# cc2540.net
KiCad netlist of a schematic drawn in EAGLE
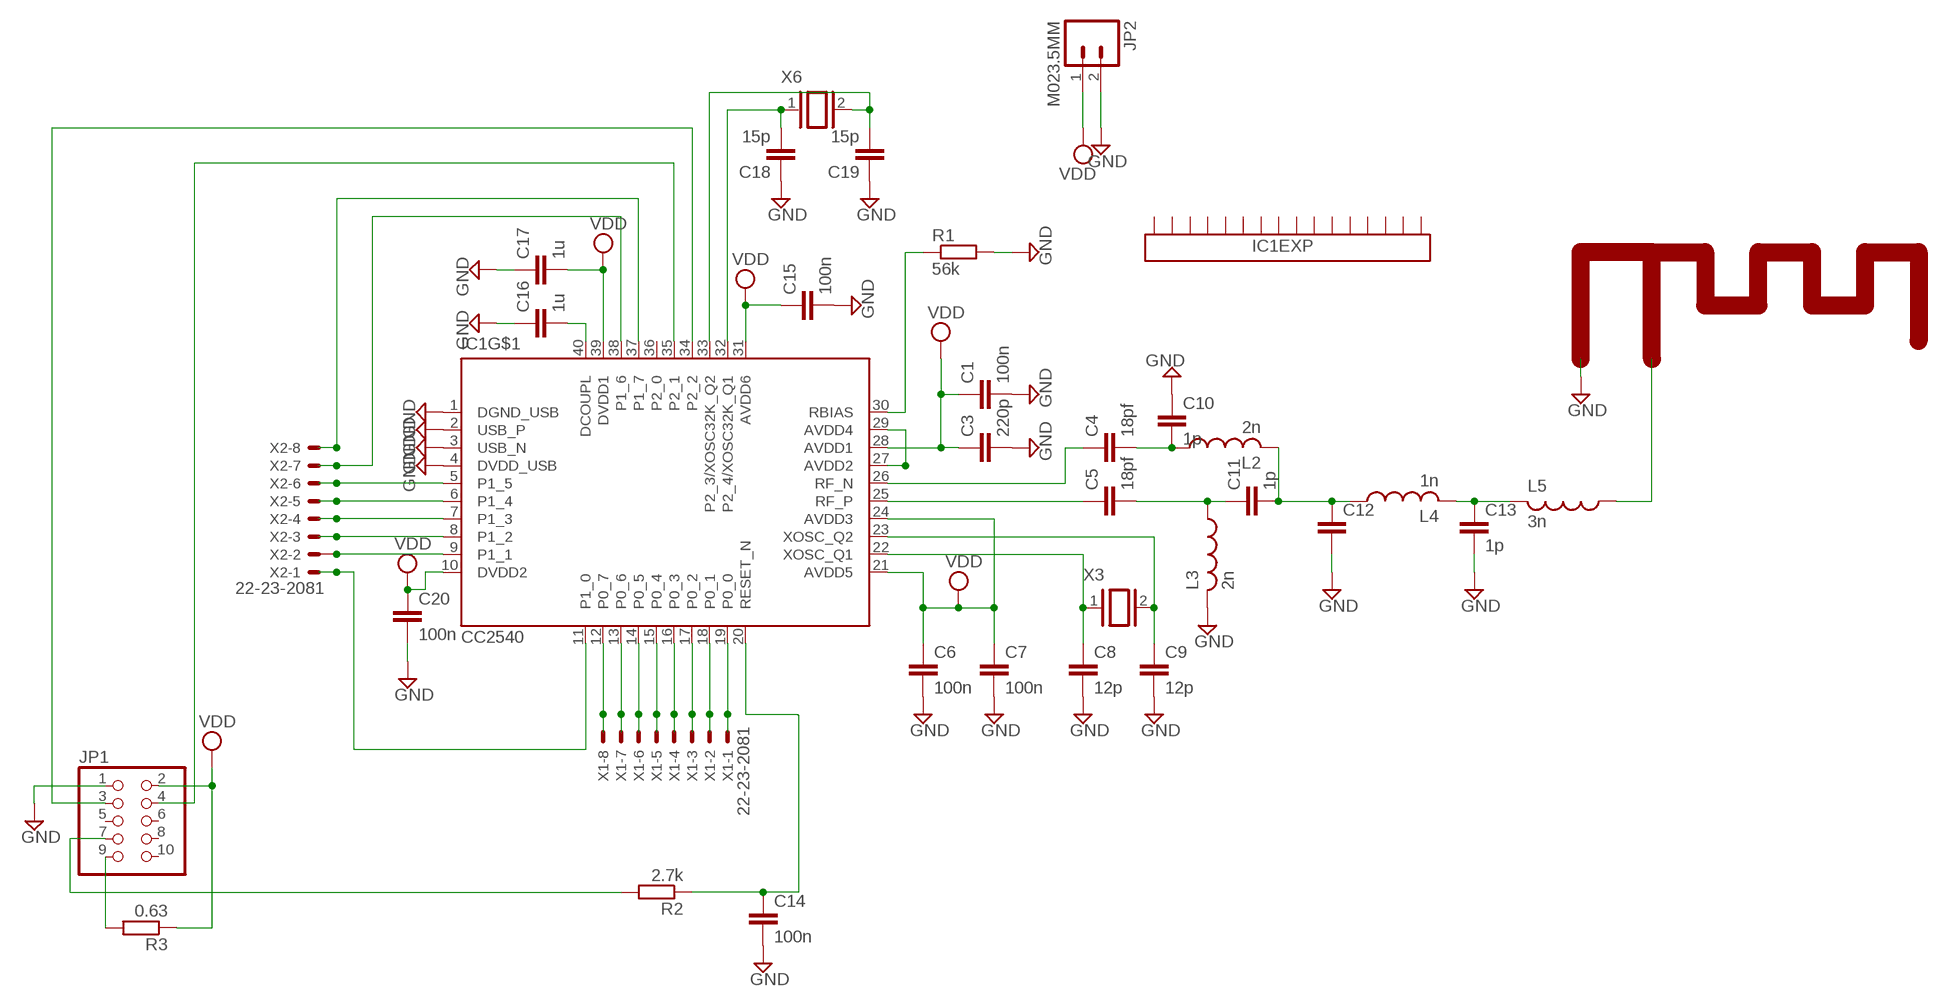
[diagram p0: schematic, sheet 1]

(export (version "E")
  (design (tool "Eeschema 10.0.6"))
  (components
    (comp (ref "A1")
      (value "TI_2.4GHZ_MIFALEFT")
      (footprint "eagle-import:TI_2.4GHZ_MIFA_LEFT")
      (libsource (lib "eagle-import") (part "TI_2.4GHZ_MIFALEFT"))
    )
    (comp (ref "C1")
      (value "100n")
      (footprint "eagle-import:C025-025X050")
      (libsource (lib "eagle-import") (part "C-EU025-025X050"))
    )
    (comp (ref "C3")
      (value "220p")
      (footprint "eagle-import:C025-025X050")
      (libsource (lib "eagle-import") (part "C-EU025-025X050"))
    )
    (comp (ref "C4")
      (value "18pf")
      (footprint "eagle-import:C025-025X050")
      (libsource (lib "eagle-import") (part "C-EU025-025X050"))
    )
    (comp (ref "C5")
      (value "18pf")
      (footprint "eagle-import:C025-025X050")
      (libsource (lib "eagle-import") (part "C-EU025-025X050"))
    )
    (comp (ref "C6")
      (value "100n")
      (footprint "eagle-import:C025-025X050")
      (libsource (lib "eagle-import") (part "C-EU025-025X050"))
    )
    (comp (ref "C7")
      (value "100n")
      (footprint "eagle-import:C025-025X050")
      (libsource (lib "eagle-import") (part "C-EU025-025X050"))
    )
    (comp (ref "C8")
      (value "12p")
      (footprint "eagle-import:C025-025X050")
      (libsource (lib "eagle-import") (part "C-EU025-025X050"))
    )
    (comp (ref "C9")
      (value "12p")
      (footprint "eagle-import:C025-025X050")
      (libsource (lib "eagle-import") (part "C-EU025-025X050"))
    )
    (comp (ref "C10")
      (value "1p")
      (footprint "eagle-import:C025-025X050")
      (libsource (lib "eagle-import") (part "C-EU025-025X050"))
    )
    (comp (ref "C11")
      (value "1p")
      (footprint "eagle-import:C025-025X050")
      (libsource (lib "eagle-import") (part "C-EU025-025X050"))
    )
    (comp (ref "C12")
      (value "C-EU025-025X050")
      (footprint "eagle-import:C025-025X050")
      (libsource (lib "eagle-import") (part "C-EU025-025X050"))
    )
    (comp (ref "C13")
      (value "1p")
      (footprint "eagle-import:C025-025X050")
      (libsource (lib "eagle-import") (part "C-EU025-025X050"))
    )
    (comp (ref "C14")
      (value "100n")
      (footprint "eagle-import:C025-025X050")
      (libsource (lib "eagle-import") (part "C-EU025-025X050"))
    )
    (comp (ref "C15")
      (value "100n")
      (footprint "eagle-import:C025-025X050")
      (libsource (lib "eagle-import") (part "C-EU025-025X050"))
    )
    (comp (ref "C16")
      (value "1u")
      (footprint "eagle-import:C025-025X050")
      (libsource (lib "eagle-import") (part "C-EU025-025X050"))
    )
    (comp (ref "C17")
      (value "1u")
      (footprint "eagle-import:C025-025X050")
      (libsource (lib "eagle-import") (part "C-EU025-025X050"))
    )
    (comp (ref "C18")
      (value "15p")
      (footprint "eagle-import:C025-025X050")
      (libsource (lib "eagle-import") (part "C-EU025-025X050"))
    )
    (comp (ref "C19")
      (value "15p")
      (footprint "eagle-import:C025-025X050")
      (libsource (lib "eagle-import") (part "C-EU025-025X050"))
    )
    (comp (ref "C20")
      (value "100n")
      (footprint "eagle-import:C025-025X050")
      (libsource (lib "eagle-import") (part "C-EU025-025X050"))
    )
    (comp (ref "IC1")
      (value "CC2540")
      (footprint "eagle-import:QFN40-6X6")
      (libsource (lib "eagle-import") (part "CC2540"))
    )
    (comp (ref "JP1")
      (value "PINHD-2X51.27_SMD")
      (footprint "eagle-import:2X05_1.27_SMD")
      (libsource (lib "eagle-import") (part "PINHD-2X51.27_SMD"))
    )
    (comp (ref "JP2")
      (value "M023.5MM")
      (footprint "eagle-import:SCREWTERMINAL-3.5MM-2")
      (libsource (lib "eagle-import") (part "M023.5MM"))
    )
    (comp (ref "L2")
      (value "2n")
      (footprint "eagle-import:0204_5")
      (libsource (lib "eagle-import") (part "L-US0204/5"))
    )
    (comp (ref "L3")
      (value "2n")
      (footprint "eagle-import:0204_5")
      (libsource (lib "eagle-import") (part "L-US0204/5"))
    )
    (comp (ref "L4")
      (value "1n")
      (footprint "eagle-import:0204_5")
      (libsource (lib "eagle-import") (part "L-US0204/5"))
    )
    (comp (ref "L5")
      (value "3n")
      (footprint "eagle-import:0204_5")
      (libsource (lib "eagle-import") (part "L-US0204/5"))
    )
    (comp (ref "R1")
      (value "56k")
      (footprint "eagle-import:0204V")
      (libsource (lib "eagle-import") (part "R-EU_0204/2V"))
    )
    (comp (ref "R2")
      (value "2.7k")
      (footprint "eagle-import:0204V")
      (libsource (lib "eagle-import") (part "R-EU_0204/2V"))
    )
    (comp (ref "R3")
      (value "0.63")
      (footprint "eagle-import:0204V")
      (libsource (lib "eagle-import") (part "R-EU_0204/2V"))
    )
    (comp (ref "X1")
      (value "22-23-2081")
      (footprint "eagle-import:22-23-2081")
      (fields (field (name "MF") "MOLEX"))
      (libsource (lib "eagle-import") (part "22-23-2081"))
    )
    (comp (ref "X2")
      (value "22-23-2081")
      (footprint "eagle-import:22-23-2081")
      (fields (field (name "MF") "MOLEX"))
      (libsource (lib "eagle-import") (part "22-23-2081"))
    )
    (comp (ref "X3")
      (value "XTAL/S")
      (footprint "eagle-import:QS")
      (libsource (lib "eagle-import") (part "XTAL/S"))
    )
    (comp (ref "X6")
      (value "XTAL/S")
      (footprint "eagle-import:QS")
      (libsource (lib "eagle-import") (part "XTAL/S"))
    )
  )
  (nets
    (net (code "1") (name "GND") (class "Default")
      (node (ref "A1") (pin "GND") (pinfunction "GND_GND") (pintype "bidirectional"))
      (node (ref "C1") (pin "2") (pinfunction "2_2") (pintype "passive"))
      (node (ref "C10") (pin "1") (pinfunction "1_1") (pintype "passive"))
      (node (ref "C12") (pin "2") (pinfunction "2_2") (pintype "passive"))
      (node (ref "C13") (pin "2") (pinfunction "2_2") (pintype "passive"))
      (node (ref "C14") (pin "2") (pinfunction "2_2") (pintype "passive"))
      (node (ref "C15") (pin "2") (pinfunction "2_2") (pintype "passive"))
      (node (ref "C16") (pin "1") (pinfunction "1_1") (pintype "passive"))
      (node (ref "C17") (pin "1") (pinfunction "1_1") (pintype "passive"))
      (node (ref "C18") (pin "1") (pinfunction "1_1") (pintype "passive"))
      (node (ref "C19") (pin "1") (pinfunction "1_1") (pintype "passive"))
      (node (ref "C20") (pin "2") (pinfunction "2_2") (pintype "passive"))
      (node (ref "C3") (pin "2") (pinfunction "2_2") (pintype "passive"))
      (node (ref "C6") (pin "2") (pinfunction "2_2") (pintype "passive"))
      (node (ref "C7") (pin "2") (pinfunction "2_2") (pintype "passive"))
      (node (ref "C8") (pin "2") (pinfunction "2_2") (pintype "passive"))
      (node (ref "C9") (pin "2") (pinfunction "2_2") (pintype "passive"))
      (node (ref "IC1") (pin "1") (pinfunction "DGND_USB_1") (pintype "power_in"))
      (node (ref "IC1") (pin "2") (pinfunction "USB_P_2") (pintype "bidirectional"))
      (node (ref "IC1") (pin "3") (pinfunction "USB_N_3") (pintype "bidirectional"))
      (node (ref "IC1") (pin "4") (pinfunction "DVDD_USB_4") (pintype "power_in"))
      (node (ref "JP1") (pin "1") (pinfunction "1_1") (pintype "passive"))
      (node (ref "JP2") (pin "2") (pinfunction "2_2") (pintype "passive"))
      (node (ref "L3") (pin "2") (pinfunction "2_2") (pintype "passive"))
      (node (ref "R1") (pin "2") (pinfunction "2_2") (pintype "passive"))
    )
    (net (code "2") (name "Net-(A1-PadFEED)") (class "Default")
      (node (ref "A1") (pin "FEED") (pinfunction "FEED_FEED") (pintype "bidirectional"))
      (node (ref "L5") (pin "1") (pinfunction "1_1") (pintype "passive"))
    )
    (net (code "3") (name "Net-(C10-Pad2)") (class "Default")
      (node (ref "C10") (pin "2") (pinfunction "2_2") (pintype "passive"))
      (node (ref "C4") (pin "2") (pinfunction "2_2") (pintype "passive"))
      (node (ref "L2") (pin "1") (pinfunction "1_1") (pintype "passive"))
    )
    (net (code "4") (name "Net-(C11-Pad1)") (class "Default")
      (node (ref "C11") (pin "1") (pinfunction "1_1") (pintype "passive"))
      (node (ref "C5") (pin "2") (pinfunction "2_2") (pintype "passive"))
      (node (ref "L3") (pin "1") (pinfunction "1_1") (pintype "passive"))
    )
    (net (code "5") (name "Net-(C11-Pad2)") (class "Default")
      (node (ref "C11") (pin "2") (pinfunction "2_2") (pintype "passive"))
      (node (ref "C12") (pin "1") (pinfunction "1_1") (pintype "passive"))
      (node (ref "L2") (pin "2") (pinfunction "2_2") (pintype "passive"))
      (node (ref "L4") (pin "1") (pinfunction "1_1") (pintype "passive"))
    )
    (net (code "6") (name "Net-(C13-Pad1)") (class "Default")
      (node (ref "C13") (pin "1") (pinfunction "1_1") (pintype "passive"))
      (node (ref "L4") (pin "2") (pinfunction "2_2") (pintype "passive"))
      (node (ref "L5") (pin "2") (pinfunction "2_2") (pintype "passive"))
    )
    (net (code "7") (name "Net-(IC1B-AVDD2)") (class "Default")
      (node (ref "IC1") (pin "27") (pinfunction "AVDD2_27") (pintype "power_in"))
      (node (ref "IC1") (pin "29") (pinfunction "AVDD4_29") (pintype "power_in"))
    )
    (net (code "8") (name "Net-(IC1B-DCOUPL)") (class "Default")
      (node (ref "C16") (pin "2") (pinfunction "2_2") (pintype "passive"))
      (node (ref "IC1") (pin "40") (pinfunction "DCOUPL_40") (pintype "power_in"))
    )
    (net (code "9") (name "Net-(IC1B-P0_0)") (class "Default")
      (node (ref "IC1") (pin "19") (pinfunction "P0_0_19") (pintype "bidirectional"))
      (node (ref "X1") (pin "1") (pinfunction "S_1") (pintype "passive"))
    )
    (net (code "10") (name "Net-(IC1B-P0_1)") (class "Default")
      (node (ref "IC1") (pin "18") (pinfunction "P0_1_18") (pintype "bidirectional"))
      (node (ref "X1") (pin "2") (pinfunction "S_2") (pintype "passive"))
    )
    (net (code "11") (name "Net-(IC1B-P0_2)") (class "Default")
      (node (ref "IC1") (pin "17") (pinfunction "P0_2_17") (pintype "bidirectional"))
      (node (ref "X1") (pin "3") (pinfunction "S_3") (pintype "passive"))
    )
    (net (code "12") (name "Net-(IC1B-P0_3)") (class "Default")
      (node (ref "IC1") (pin "16") (pinfunction "P0_3_16") (pintype "bidirectional"))
      (node (ref "X1") (pin "4") (pinfunction "S_4") (pintype "passive"))
    )
    (net (code "13") (name "Net-(IC1B-P0_4)") (class "Default")
      (node (ref "IC1") (pin "15") (pinfunction "P0_4_15") (pintype "bidirectional"))
      (node (ref "X1") (pin "5") (pinfunction "S_5") (pintype "passive"))
    )
    (net (code "14") (name "Net-(IC1B-P0_5)") (class "Default")
      (node (ref "IC1") (pin "14") (pinfunction "P0_5_14") (pintype "bidirectional"))
      (node (ref "X1") (pin "6") (pinfunction "S_6") (pintype "passive"))
    )
    (net (code "15") (name "Net-(IC1B-P0_6)") (class "Default")
      (node (ref "IC1") (pin "13") (pinfunction "P0_6_13") (pintype "bidirectional"))
      (node (ref "X1") (pin "7") (pinfunction "S_7") (pintype "passive"))
    )
    (net (code "16") (name "Net-(IC1B-P0_7)") (class "Default")
      (node (ref "IC1") (pin "12") (pinfunction "P0_7_12") (pintype "bidirectional"))
      (node (ref "X1") (pin "8") (pinfunction "S_8") (pintype "passive"))
    )
    (net (code "17") (name "Net-(IC1B-P1_0)") (class "Default")
      (node (ref "IC1") (pin "11") (pinfunction "P1_0_11") (pintype "bidirectional"))
      (node (ref "X2") (pin "1") (pinfunction "S_1") (pintype "passive"))
    )
    (net (code "18") (name "Net-(IC1B-P1_1)") (class "Default")
      (node (ref "IC1") (pin "9") (pinfunction "P1_1_9") (pintype "bidirectional"))
      (node (ref "X2") (pin "2") (pinfunction "S_2") (pintype "passive"))
    )
    (net (code "19") (name "Net-(IC1B-P1_2)") (class "Default")
      (node (ref "IC1") (pin "8") (pinfunction "P1_2_8") (pintype "bidirectional"))
      (node (ref "X2") (pin "3") (pinfunction "S_3") (pintype "passive"))
    )
    (net (code "20") (name "Net-(IC1B-P1_3)") (class "Default")
      (node (ref "IC1") (pin "7") (pinfunction "P1_3_7") (pintype "bidirectional"))
      (node (ref "X2") (pin "4") (pinfunction "S_4") (pintype "passive"))
    )
    (net (code "21") (name "Net-(IC1B-P1_4)") (class "Default")
      (node (ref "IC1") (pin "6") (pinfunction "P1_4_6") (pintype "bidirectional"))
      (node (ref "X2") (pin "5") (pinfunction "S_5") (pintype "passive"))
    )
    (net (code "22") (name "Net-(IC1B-P1_5)") (class "Default")
      (node (ref "IC1") (pin "5") (pinfunction "P1_5_5") (pintype "bidirectional"))
      (node (ref "X2") (pin "6") (pinfunction "S_6") (pintype "passive"))
    )
    (net (code "23") (name "Net-(IC1B-P1_6)") (class "Default")
      (node (ref "IC1") (pin "38") (pinfunction "P1_6_38") (pintype "bidirectional"))
      (node (ref "X2") (pin "7") (pinfunction "S_7") (pintype "passive"))
    )
    (net (code "24") (name "Net-(IC1B-P1_7)") (class "Default")
      (node (ref "IC1") (pin "37") (pinfunction "P1_7_37") (pintype "bidirectional"))
      (node (ref "X2") (pin "8") (pinfunction "S_8") (pintype "passive"))
    )
    (net (code "25") (name "Net-(IC1B-P2_1)") (class "Default")
      (node (ref "IC1") (pin "35") (pinfunction "P2_1_35") (pintype "bidirectional"))
      (node (ref "JP1") (pin "4") (pinfunction "4_4") (pintype "passive"))
    )
    (net (code "26") (name "Net-(IC1B-P2_2)") (class "Default")
      (node (ref "IC1") (pin "34") (pinfunction "P2_2_34") (pintype "bidirectional"))
      (node (ref "JP1") (pin "3") (pinfunction "3_3") (pintype "passive"))
    )
    (net (code "27") (name "Net-(IC1B-P2_3{slash}XOSC32K_Q2)") (class "Default")
      (node (ref "C19") (pin "2") (pinfunction "2_2") (pintype "passive"))
      (node (ref "IC1") (pin "33") (pinfunction "P2_3/XOSC32K_Q2_33") (pintype "bidirectional"))
      (node (ref "X6") (pin "2") (pinfunction "2_2") (pintype "passive"))
    )
    (net (code "28") (name "Net-(IC1B-P2_4{slash}XOSC32K_Q1)") (class "Default")
      (node (ref "C18") (pin "2") (pinfunction "2_2") (pintype "passive"))
      (node (ref "IC1") (pin "32") (pinfunction "P2_4/XOSC32K_Q1_32") (pintype "bidirectional"))
      (node (ref "X6") (pin "1") (pinfunction "1_1") (pintype "passive"))
    )
    (net (code "29") (name "Net-(IC1B-RBIAS)") (class "Default")
      (node (ref "IC1") (pin "30") (pinfunction "RBIAS_30") (pintype "bidirectional"))
      (node (ref "R1") (pin "1") (pinfunction "1_1") (pintype "passive"))
    )
    (net (code "30") (name "Net-(IC1B-RESET_N)") (class "Default")
      (node (ref "C14") (pin "1") (pinfunction "1_1") (pintype "passive"))
      (node (ref "IC1") (pin "20") (pinfunction "RESET_N_20") (pintype "input"))
      (node (ref "R2") (pin "1") (pinfunction "1_1") (pintype "passive"))
    )
    (net (code "31") (name "Net-(IC1B-RF_N)") (class "Default")
      (node (ref "C4") (pin "1") (pinfunction "1_1") (pintype "passive"))
      (node (ref "IC1") (pin "26") (pinfunction "RF_N_26") (pintype "input"))
    )
    (net (code "32") (name "Net-(IC1B-RF_P)") (class "Default")
      (node (ref "C5") (pin "1") (pinfunction "1_1") (pintype "passive"))
      (node (ref "IC1") (pin "25") (pinfunction "RF_P_25") (pintype "input"))
    )
    (net (code "33") (name "Net-(IC1B-XOSC_Q1)") (class "Default")
      (node (ref "C8") (pin "1") (pinfunction "1_1") (pintype "passive"))
      (node (ref "IC1") (pin "22") (pinfunction "XOSC_Q1_22") (pintype "bidirectional"))
      (node (ref "X3") (pin "1") (pinfunction "1_1") (pintype "passive"))
    )
    (net (code "34") (name "Net-(IC1B-XOSC_Q2)") (class "Default")
      (node (ref "C9") (pin "1") (pinfunction "1_1") (pintype "passive"))
      (node (ref "IC1") (pin "23") (pinfunction "XOSC_Q2_23") (pintype "bidirectional"))
      (node (ref "X3") (pin "2") (pinfunction "2_2") (pintype "passive"))
    )
    (net (code "35") (name "Net-(JP1-Pad7)") (class "Default")
      (node (ref "JP1") (pin "7") (pinfunction "7_7") (pintype "passive"))
      (node (ref "R2") (pin "2") (pinfunction "2_2") (pintype "passive"))
    )
    (net (code "36") (name "Net-(JP1-Pad9)") (class "Default")
      (node (ref "JP1") (pin "9") (pinfunction "9_9") (pintype "passive"))
      (node (ref "R3") (pin "2") (pinfunction "2_2") (pintype "passive"))
    )
    (net (code "37") (name "VDD") (class "Default")
      (node (ref "C1") (pin "1") (pinfunction "1_1") (pintype "passive"))
      (node (ref "C15") (pin "1") (pinfunction "1_1") (pintype "passive"))
      (node (ref "C17") (pin "2") (pinfunction "2_2") (pintype "passive"))
      (node (ref "C20") (pin "1") (pinfunction "1_1") (pintype "passive"))
      (node (ref "C3") (pin "1") (pinfunction "1_1") (pintype "passive"))
      (node (ref "C6") (pin "1") (pinfunction "1_1") (pintype "passive"))
      (node (ref "C7") (pin "1") (pinfunction "1_1") (pintype "passive"))
      (node (ref "IC1") (pin "10") (pinfunction "DVDD2_10") (pintype "power_in"))
      (node (ref "IC1") (pin "21") (pinfunction "AVDD5_21") (pintype "power_in"))
      (node (ref "IC1") (pin "24") (pinfunction "AVDD3_24") (pintype "power_in"))
      (node (ref "IC1") (pin "28") (pinfunction "AVDD1_28") (pintype "power_in"))
      (node (ref "IC1") (pin "31") (pinfunction "AVDD6_31") (pintype "power_in"))
      (node (ref "IC1") (pin "39") (pinfunction "DVDD1_39") (pintype "power_in"))
      (node (ref "JP1") (pin "2") (pinfunction "2_2") (pintype "passive"))
      (node (ref "JP2") (pin "1") (pinfunction "1_1") (pintype "passive"))
      (node (ref "R3") (pin "1") (pinfunction "1_1") (pintype "passive"))
    )
    (net (code "38") (name "unconnected-(IC1A-EXP16-PadEXP@1)") (class "Default")
      (node (ref "IC1") (pin "EXP@1") (pinfunction "EXP16_EXP@1") (pintype "input"))
    )
    (net (code "39") (name "unconnected-(IC1A-EXP16-PadEXP@2)") (class "Default")
      (node (ref "IC1") (pin "EXP@2") (pinfunction "EXP16_EXP@2") (pintype "input"))
    )
    (net (code "40") (name "unconnected-(IC1A-EXP16-PadEXP@3)") (class "Default")
      (node (ref "IC1") (pin "EXP@3") (pinfunction "EXP16_EXP@3") (pintype "input"))
    )
    (net (code "41") (name "unconnected-(IC1A-EXP16-PadEXP@4)") (class "Default")
      (node (ref "IC1") (pin "EXP@4") (pinfunction "EXP16_EXP@4") (pintype "input"))
    )
    (net (code "42") (name "unconnected-(IC1A-EXP16-PadEXP@5)") (class "Default")
      (node (ref "IC1") (pin "EXP@5") (pinfunction "EXP16_EXP@5") (pintype "input"))
    )
    (net (code "43") (name "unconnected-(IC1A-EXP16-PadEXP@6)") (class "Default")
      (node (ref "IC1") (pin "EXP@6") (pinfunction "EXP16_EXP@6") (pintype "input"))
    )
    (net (code "44") (name "unconnected-(IC1A-EXP16-PadEXP@7)") (class "Default")
      (node (ref "IC1") (pin "EXP@7") (pinfunction "EXP16_EXP@7") (pintype "input"))
    )
    (net (code "45") (name "unconnected-(IC1A-EXP16-PadEXP@8)") (class "Default")
      (node (ref "IC1") (pin "EXP@8") (pinfunction "EXP16_EXP@8") (pintype "input"))
    )
    (net (code "46") (name "unconnected-(IC1A-EXP16-PadEXP@9)") (class "Default")
      (node (ref "IC1") (pin "EXP@9") (pinfunction "EXP16_EXP@9") (pintype "input"))
    )
    (net (code "47") (name "unconnected-(IC1A-EXP16-PadEXP@10)") (class "Default")
      (node (ref "IC1") (pin "EXP@10") (pinfunction "EXP16_EXP@10") (pintype "input"))
    )
    (net (code "48") (name "unconnected-(IC1A-EXP16-PadEXP@11)") (class "Default")
      (node (ref "IC1") (pin "EXP@11") (pinfunction "EXP16_EXP@11") (pintype "input"))
    )
    (net (code "49") (name "unconnected-(IC1A-EXP16-PadEXP@12)") (class "Default")
      (node (ref "IC1") (pin "EXP@12") (pinfunction "EXP16_EXP@12") (pintype "input"))
    )
    (net (code "50") (name "unconnected-(IC1A-EXP16-PadEXP@13)") (class "Default")
      (node (ref "IC1") (pin "EXP@13") (pinfunction "EXP16_EXP@13") (pintype "input"))
    )
    (net (code "51") (name "unconnected-(IC1A-EXP16-PadEXP@14)") (class "Default")
      (node (ref "IC1") (pin "EXP@14") (pinfunction "EXP16_EXP@14") (pintype "input"))
    )
    (net (code "52") (name "unconnected-(IC1A-EXP16-PadEXP@15)") (class "Default")
      (node (ref "IC1") (pin "EXP@15") (pinfunction "EXP16_EXP@15") (pintype "input"))
    )
    (net (code "53") (name "unconnected-(IC1A-EXP16-PadEXP@16)") (class "Default")
      (node (ref "IC1") (pin "EXP@16") (pinfunction "EXP16_EXP@16") (pintype "input"))
    )
    (net (code "54") (name "unconnected-(IC1B-P2_0-Pad36)") (class "Default")
      (node (ref "IC1") (pin "36") (pinfunction "P2_0_36") (pintype "bidirectional"))
    )
    (net (code "55") (name "unconnected-(JP1-Pad5)") (class "Default")
      (node (ref "JP1") (pin "5") (pinfunction "5_5") (pintype "passive"))
    )
    (net (code "56") (name "unconnected-(JP1-Pad6)") (class "Default")
      (node (ref "JP1") (pin "6") (pinfunction "6_6") (pintype "passive"))
    )
    (net (code "57") (name "unconnected-(JP1-Pad8)") (class "Default")
      (node (ref "JP1") (pin "8") (pinfunction "8_8") (pintype "passive"))
    )
    (net (code "58") (name "unconnected-(JP1-Pad10)") (class "Default")
      (node (ref "JP1") (pin "10") (pinfunction "10_10") (pintype "passive"))
    )
  )
)
